# Sheet_1_copy.net
KiCad netlist of a schematic drawn in Altium Designer
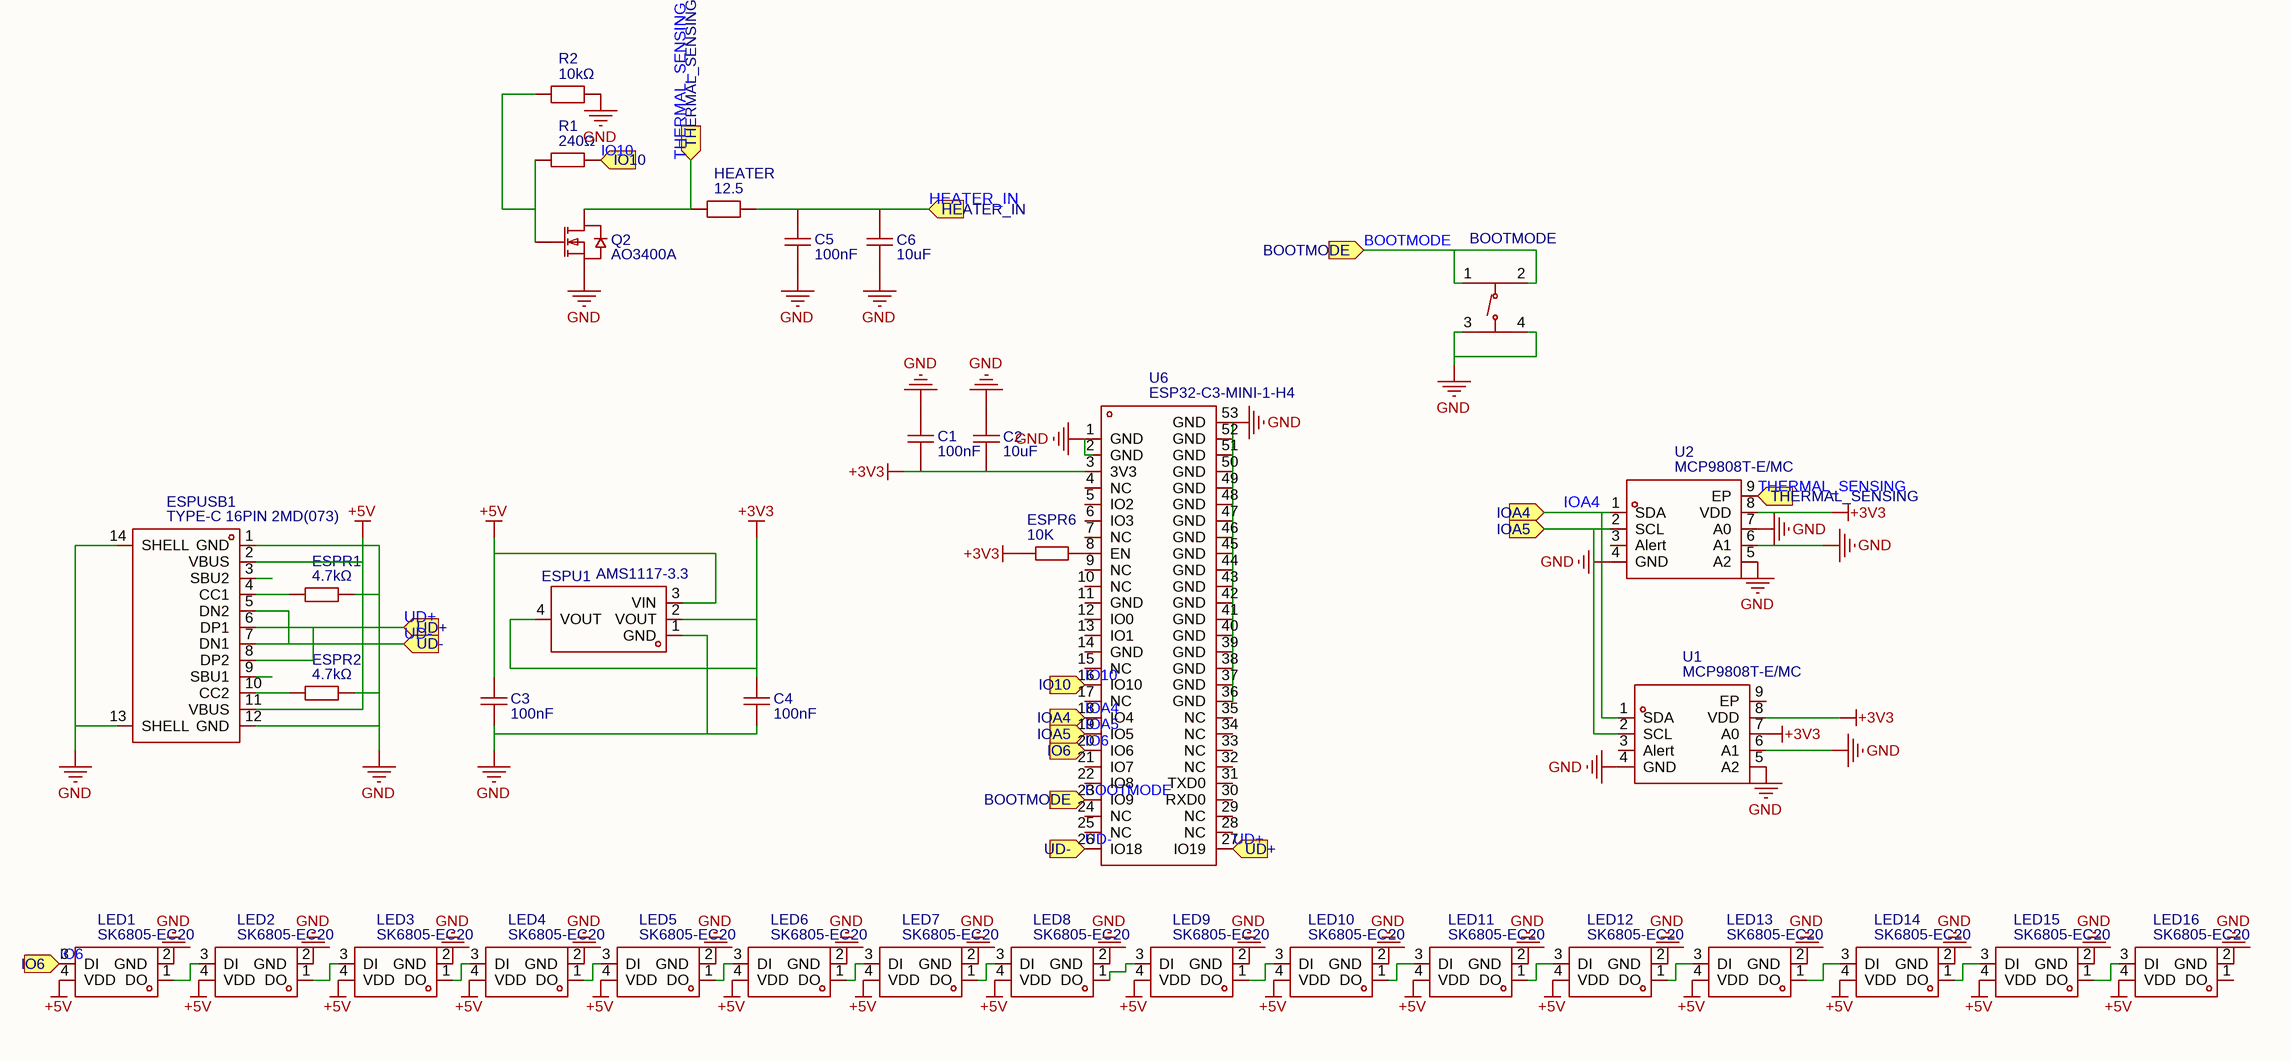
[diagram p0: Sheet_1 copy.schdoc]

(export (version "E")
  (design (tool "Eeschema 10.0.6"))
  (components
    (comp (ref "BOOTMODE")
      (value "TS-1187A-B-A-B")
      (footprint "SW-SMD_4P-L5.1-W5.1-P3.70-LS6.5-TL-2")
      (fields (field (name "MANUFACTURER") "XKB Connectivity(中国星坤)") (field (name "CONTRIBUTOR") "LCSC"))
      (libsource (lib "altium-import") (part "root_0_TS-1187A-B-A-B_"))
    )
    (comp (ref "C1")
      (value "100nF")
      (footprint "C0603")
      (fields
        (field (name "MANUFACTURER") "SAMSUNG(三星)")
        (field (name "MANUFACTURER PART") "CL10B104KB8NNNC")
      )
      (libsource (lib "altium-import") (part "root_1_100nF_"))
    )
    (comp (ref "C2")
      (value "10uF")
      (footprint "C0805")
      (fields
        (field (name "MANUFACTURER PART") "CL21A106KAYNNNE")
        (field (name "MANUFACTURER") "SAMSUNG(三星)")
      )
      (libsource (lib "altium-import") (part "root_3_10uF_"))
    )
    (comp (ref "C3")
      (value "100nF")
      (footprint "C0603")
      (fields
        (field (name "MANUFACTURER") "SAMSUNG(三星)")
        (field (name "MANUFACTURER PART") "CL10B104KB8NNNC")
      )
      (libsource (lib "altium-import") (part "root_1_100nF_"))
    )
    (comp (ref "C4")
      (value "100nF")
      (footprint "C0603")
      (fields
        (field (name "MANUFACTURER") "SAMSUNG(三星)")
        (field (name "MANUFACTURER PART") "CL10B104KB8NNNC")
      )
      (libsource (lib "altium-import") (part "root_1_100nF_"))
    )
    (comp (ref "C5")
      (value "100nF")
      (footprint "C0603")
      (fields
        (field (name "MANUFACTURER") "SAMSUNG(三星)")
        (field (name "MANUFACTURER PART") "CL10B104KB8NNNC")
      )
      (libsource (lib "altium-import") (part "root_1_100nF_"))
    )
    (comp (ref "C6")
      (value "10uF")
      (footprint "C0805")
      (fields
        (field (name "MANUFACTURER PART") "CL21A106KAYNNNE")
        (field (name "MANUFACTURER") "SAMSUNG(三星)")
      )
      (libsource (lib "altium-import") (part "root_3_10uF_"))
    )
    (comp (ref "ESPR1")
      (value "4.7kΩ")
      (footprint "R0402")
      (fields (field (name "MANUFACTURER") "UniOhm") (field (name "MANUFACTURER PART") "0402WGF4701TCE"))
      (libsource (lib "altium-import") (part "root_0_4.7kΩ_"))
    )
    (comp (ref "ESPR2")
      (value "4.7kΩ")
      (footprint "R0402")
      (fields (field (name "MANUFACTURER") "UniOhm") (field (name "MANUFACTURER PART") "0402WGF4701TCE"))
      (libsource (lib "altium-import") (part "root_0_4.7kΩ_"))
    )
    (comp (ref "ESPR6")
      (value "10K")
      (footprint "R0402")
      (fields (field (name "MANUFACTURER") "UniOhm") (field (name "MANUFACTURER PART") "0402WGF1002TCE"))
      (libsource (lib "altium-import") (part "root_2_10K_"))
    )
    (comp (ref "ESPU1")
      (value "AMS1117-3.3")
      (footprint "SOT-223-3_L6.5-W3.4-P2.30-LS7.0-BR")
      (fields (field (name "MANUFACTURER") "AMS"))
      (libsource (lib "altium-import") (part "root_0_AMS1117-3.3_"))
    )
    (comp (ref "ESPUSB1")
      (value "TYPE-C 16PIN 2MD(073)")
      (footprint "USB-C-SMD_TYPE-C-6PIN-2MD-073")
      (fields (field (name "MANUFACTURER") "SHOU HAN(首韩)") (field (name "CONTRIBUTOR") "LCSC"))
      (libsource (lib "altium-import") (part "root_2_TYPE-C 16PIN 2MD(073)_"))
    )
    (comp (ref "HEATER")
      (value "12.5")
      (fields (field (name "CONTRIBUTOR") "LCEDA_Lib"))
      (libsource (lib "altium-import") (part "root_0_12.5_"))
    )
    (comp (ref "LED1")
      (value "SK6805-EC20")
      (footprint "LED-SMD_4P-L2.0-W2.0-TL_WS2812B-2020")
      (fields (field (name "MANUFACTURER") "OPSCO Optoelectronics") (field (name "CONTRIBUTOR") "LCSC"))
      (libsource (lib "altium-import") (part "root_2_SK6805-EC20_"))
    )
    (comp (ref "LED2")
      (value "SK6805-EC20")
      (footprint "LED-SMD_4P-L2.0-W2.0-TL_WS2812B-2020")
      (fields (field (name "MANUFACTURER") "OPSCO Optoelectronics") (field (name "CONTRIBUTOR") "LCSC"))
      (libsource (lib "altium-import") (part "root_2_SK6805-EC20_"))
    )
    (comp (ref "LED3")
      (value "SK6805-EC20")
      (footprint "LED-SMD_4P-L2.0-W2.0-TL_WS2812B-2020")
      (fields (field (name "MANUFACTURER") "OPSCO Optoelectronics") (field (name "CONTRIBUTOR") "LCSC"))
      (libsource (lib "altium-import") (part "root_2_SK6805-EC20_"))
    )
    (comp (ref "LED4")
      (value "SK6805-EC20")
      (footprint "LED-SMD_4P-L2.0-W2.0-TL_WS2812B-2020")
      (fields (field (name "MANUFACTURER") "OPSCO Optoelectronics") (field (name "CONTRIBUTOR") "LCSC"))
      (libsource (lib "altium-import") (part "root_2_SK6805-EC20_"))
    )
    (comp (ref "LED5")
      (value "SK6805-EC20")
      (footprint "LED-SMD_4P-L2.0-W2.0-TL_WS2812B-2020")
      (fields (field (name "MANUFACTURER") "OPSCO Optoelectronics") (field (name "CONTRIBUTOR") "LCSC"))
      (libsource (lib "altium-import") (part "root_2_SK6805-EC20_"))
    )
    (comp (ref "LED6")
      (value "SK6805-EC20")
      (footprint "LED-SMD_4P-L2.0-W2.0-TL_WS2812B-2020")
      (fields (field (name "MANUFACTURER") "OPSCO Optoelectronics") (field (name "CONTRIBUTOR") "LCSC"))
      (libsource (lib "altium-import") (part "root_2_SK6805-EC20_"))
    )
    (comp (ref "LED7")
      (value "SK6805-EC20")
      (footprint "LED-SMD_4P-L2.0-W2.0-TL_WS2812B-2020")
      (fields (field (name "MANUFACTURER") "OPSCO Optoelectronics") (field (name "CONTRIBUTOR") "LCSC"))
      (libsource (lib "altium-import") (part "root_2_SK6805-EC20_"))
    )
    (comp (ref "LED8")
      (value "SK6805-EC20")
      (footprint "LED-SMD_4P-L2.0-W2.0-TL_WS2812B-2020")
      (fields (field (name "MANUFACTURER") "OPSCO Optoelectronics") (field (name "CONTRIBUTOR") "LCSC"))
      (libsource (lib "altium-import") (part "root_2_SK6805-EC20_"))
    )
    (comp (ref "LED9")
      (value "SK6805-EC20")
      (footprint "LED-SMD_4P-L2.0-W2.0-TL_WS2812B-2020")
      (fields (field (name "MANUFACTURER") "OPSCO Optoelectronics") (field (name "CONTRIBUTOR") "LCSC"))
      (libsource (lib "altium-import") (part "root_2_SK6805-EC20_"))
    )
    (comp (ref "LED10")
      (value "SK6805-EC20")
      (footprint "LED-SMD_4P-L2.0-W2.0-TL_WS2812B-2020")
      (fields (field (name "MANUFACTURER") "OPSCO Optoelectronics") (field (name "CONTRIBUTOR") "LCSC"))
      (libsource (lib "altium-import") (part "root_2_SK6805-EC20_"))
    )
    (comp (ref "LED11")
      (value "SK6805-EC20")
      (footprint "LED-SMD_4P-L2.0-W2.0-TL_WS2812B-2020")
      (fields (field (name "MANUFACTURER") "OPSCO Optoelectronics") (field (name "CONTRIBUTOR") "LCSC"))
      (libsource (lib "altium-import") (part "root_2_SK6805-EC20_"))
    )
    (comp (ref "LED12")
      (value "SK6805-EC20")
      (footprint "LED-SMD_4P-L2.0-W2.0-TL_WS2812B-2020")
      (fields (field (name "MANUFACTURER") "OPSCO Optoelectronics") (field (name "CONTRIBUTOR") "LCSC"))
      (libsource (lib "altium-import") (part "root_2_SK6805-EC20_"))
    )
    (comp (ref "LED13")
      (value "SK6805-EC20")
      (footprint "LED-SMD_4P-L2.0-W2.0-TL_WS2812B-2020")
      (fields (field (name "MANUFACTURER") "OPSCO Optoelectronics") (field (name "CONTRIBUTOR") "LCSC"))
      (libsource (lib "altium-import") (part "root_2_SK6805-EC20_"))
    )
    (comp (ref "LED14")
      (value "SK6805-EC20")
      (footprint "LED-SMD_4P-L2.0-W2.0-TL_WS2812B-2020")
      (fields (field (name "MANUFACTURER") "OPSCO Optoelectronics") (field (name "CONTRIBUTOR") "LCSC"))
      (libsource (lib "altium-import") (part "root_2_SK6805-EC20_"))
    )
    (comp (ref "LED15")
      (value "SK6805-EC20")
      (footprint "LED-SMD_4P-L2.0-W2.0-TL_WS2812B-2020")
      (fields (field (name "MANUFACTURER") "OPSCO Optoelectronics") (field (name "CONTRIBUTOR") "LCSC"))
      (libsource (lib "altium-import") (part "root_2_SK6805-EC20_"))
    )
    (comp (ref "LED16")
      (value "SK6805-EC20")
      (footprint "LED-SMD_4P-L2.0-W2.0-TL_WS2812B-2020")
      (fields (field (name "MANUFACTURER") "OPSCO Optoelectronics") (field (name "CONTRIBUTOR") "LCSC"))
      (libsource (lib "altium-import") (part "root_2_SK6805-EC20_"))
    )
    (comp (ref "Q2")
      (value "AO3400A")
      (footprint "SOT-23-3_L2.9-W1.3-P1.90-LS2.4-BR")
      (fields (field (name "MANUFACTURER") "AOS"))
      (libsource (lib "altium-import") (part "root_0_AO3400A_"))
    )
    (comp (ref "R1")
      (value "240Ω")
      (footprint "R0805")
      (fields (field (name "MANUFACTURER") "LIZ(丽智电子)") (field (name "MANUFACTURER PART") "CR0805J80241G"))
      (libsource (lib "altium-import") (part "root_0_240Ω_"))
    )
    (comp (ref "R2")
      (value "10kΩ")
      (footprint "R0805")
      (fields
        (field (name "MANUFACTURER") "Walsin(华新科)")
        (field (name "MANUFACTURER PART") "MR08X1002FTL")
        (field (name "CONTRIBUTOR") "LCSC")
      )
      (libsource (lib "altium-import") (part "root_0_10kΩ_"))
    )
    (comp (ref "U1")
      (value "MCP9808T-E/MC")
      (footprint "DFN-8_L3.0-W2.0-P0.50-TL-EP-1")
      (fields (field (name "MANUFACTURER") "MICROCHIP(美国微芯)") (field (name "CONTRIBUTOR") "lcsc"))
      (libsource (lib "altium-import") (part "root_0_MCP9808T-E/MC_"))
    )
    (comp (ref "U2")
      (value "MCP9808T-E/MC")
      (footprint "DFN-8_L3.0-W2.0-P0.50-TL-EP-1")
      (fields (field (name "MANUFACTURER") "MICROCHIP(美国微芯)") (field (name "CONTRIBUTOR") "lcsc"))
      (libsource (lib "altium-import") (part "root_0_MCP9808T-E/MC_"))
    )
    (comp (ref "U6")
      (value "ESP32-C3-MINI-1-H4")
      (footprint "WIFIM-SMD_ESP32-C3-MINI-1")
      (fields (field (name "MANUFACTURER") "ESPRESSIF(乐鑫)") (field (name "CONTRIBUTOR") "LCSC"))
      (libsource (lib "altium-import") (part "root_0_ESP32-C3-MINI-1-H4_"))
    )
  )
  (nets
    (net (code "1") (name "+3V3") (class "Default")
      (node (ref "C1") (pin "1") (pinfunction "1_1") (pintype "passive"))
      (node (ref "C2") (pin "2") (pinfunction "2_2") (pintype "passive"))
      (node (ref "C4") (pin "2") (pinfunction "2_2") (pintype "passive"))
      (node (ref "ESPR6") (pin "2") (pinfunction "2_2") (pintype "passive"))
      (node (ref "ESPU1") (pin "2") (pinfunction "VOUT_2") (pintype "passive"))
      (node (ref "ESPU1") (pin "4") (pinfunction "VOUT_4") (pintype "passive"))
      (node (ref "U1") (pin "7") (pinfunction "A0_7") (pintype "passive"))
      (node (ref "U1") (pin "8") (pinfunction "VDD_8") (pintype "passive"))
      (node (ref "U2") (pin "8") (pinfunction "VDD_8") (pintype "passive"))
      (node (ref "U6") (pin "3") (pinfunction "3V3_3") (pintype "passive"))
    )
    (net (code "2") (name "+5V") (class "Default")
      (node (ref "C3") (pin "2") (pinfunction "2_2") (pintype "passive"))
      (node (ref "ESPU1") (pin "3") (pinfunction "VIN_3") (pintype "passive"))
      (node (ref "ESPUSB1") (pin "11") (pinfunction "VBUS_11") (pintype "passive"))
      (node (ref "ESPUSB1") (pin "2") (pinfunction "VBUS_2") (pintype "passive"))
      (node (ref "LED1") (pin "4") (pinfunction "VDD_4") (pintype "passive"))
      (node (ref "LED10") (pin "4") (pinfunction "VDD_4") (pintype "passive"))
      (node (ref "LED11") (pin "4") (pinfunction "VDD_4") (pintype "passive"))
      (node (ref "LED12") (pin "4") (pinfunction "VDD_4") (pintype "passive"))
      (node (ref "LED13") (pin "4") (pinfunction "VDD_4") (pintype "passive"))
      (node (ref "LED14") (pin "4") (pinfunction "VDD_4") (pintype "passive"))
      (node (ref "LED15") (pin "4") (pinfunction "VDD_4") (pintype "passive"))
      (node (ref "LED16") (pin "4") (pinfunction "VDD_4") (pintype "passive"))
      (node (ref "LED2") (pin "4") (pinfunction "VDD_4") (pintype "passive"))
      (node (ref "LED3") (pin "4") (pinfunction "VDD_4") (pintype "passive"))
      (node (ref "LED4") (pin "4") (pinfunction "VDD_4") (pintype "passive"))
      (node (ref "LED5") (pin "4") (pinfunction "VDD_4") (pintype "passive"))
      (node (ref "LED6") (pin "4") (pinfunction "VDD_4") (pintype "passive"))
      (node (ref "LED7") (pin "4") (pinfunction "VDD_4") (pintype "passive"))
      (node (ref "LED8") (pin "4") (pinfunction "VDD_4") (pintype "passive"))
      (node (ref "LED9") (pin "4") (pinfunction "VDD_4") (pintype "passive"))
    )
    (net (code "3") (name "/BOOTMODE") (class "Default")
      (node (ref "BOOTMODE") (pin "1") (pinfunction "A_1") (pintype "passive"))
      (node (ref "BOOTMODE") (pin "2") (pinfunction "B_2") (pintype "passive"))
      (node (ref "U6") (pin "23") (pinfunction "IO9_23") (pintype "passive"))
    )
    (net (code "4") (name "/HEATER_IN") (class "Default")
      (node (ref "C5") (pin "2") (pinfunction "2_2") (pintype "passive"))
      (node (ref "C6") (pin "1") (pinfunction "1_1") (pintype "passive"))
      (node (ref "HEATER") (pin "2") (pinfunction "2_2") (pintype "passive"))
    )
    (net (code "5") (name "/IO6") (class "Default")
      (node (ref "LED1") (pin "3") (pinfunction "DI_3") (pintype "passive"))
      (node (ref "U6") (pin "20") (pinfunction "IO6_20") (pintype "passive"))
    )
    (net (code "6") (name "/IO10") (class "Default")
      (node (ref "R1") (pin "2") (pinfunction "2_2") (pintype "passive"))
      (node (ref "U6") (pin "16") (pinfunction "IO10_16") (pintype "passive"))
    )
    (net (code "7") (name "/IOA4") (class "Default")
      (node (ref "U1") (pin "1") (pinfunction "SDA_1") (pintype "passive"))
      (node (ref "U2") (pin "1") (pinfunction "SDA_1") (pintype "passive"))
      (node (ref "U6") (pin "18") (pinfunction "IO4_18") (pintype "passive"))
    )
    (net (code "8") (name "/IOA5") (class "Default")
      (node (ref "U1") (pin "2") (pinfunction "SCL_2") (pintype "passive"))
      (node (ref "U2") (pin "2") (pinfunction "SCL_2") (pintype "passive"))
      (node (ref "U6") (pin "19") (pinfunction "IO5_19") (pintype "passive"))
    )
    (net (code "9") (name "/THERMAL_SENSING") (class "Default")
      (node (ref "HEATER") (pin "1") (pinfunction "1_1") (pintype "passive"))
      (node (ref "Q2") (pin "3") (pinfunction "D_3") (pintype "passive"))
      (node (ref "U2") (pin "9") (pinfunction "EP_9") (pintype "passive"))
    )
    (net (code "10") (name "/UD+") (class "Default")
      (node (ref "ESPUSB1") (pin "6") (pinfunction "DP1_6") (pintype "passive"))
      (node (ref "ESPUSB1") (pin "8") (pinfunction "DP2_8") (pintype "passive"))
      (node (ref "U6") (pin "27") (pinfunction "IO19_27") (pintype "passive"))
    )
    (net (code "11") (name "/UD-") (class "Default")
      (node (ref "ESPUSB1") (pin "5") (pinfunction "DN2_5") (pintype "passive"))
      (node (ref "ESPUSB1") (pin "7") (pinfunction "DN1_7") (pintype "passive"))
      (node (ref "U6") (pin "26") (pinfunction "IO18_26") (pintype "passive"))
    )
    (net (code "12") (name "GND") (class "Default")
      (node (ref "BOOTMODE") (pin "3") (pinfunction "C_3") (pintype "passive"))
      (node (ref "BOOTMODE") (pin "4") (pinfunction "D_4") (pintype "passive"))
      (node (ref "C1") (pin "2") (pinfunction "2_2") (pintype "passive"))
      (node (ref "C2") (pin "1") (pinfunction "1_1") (pintype "passive"))
      (node (ref "C3") (pin "1") (pinfunction "1_1") (pintype "passive"))
      (node (ref "C4") (pin "1") (pinfunction "1_1") (pintype "passive"))
      (node (ref "C5") (pin "1") (pinfunction "1_1") (pintype "passive"))
      (node (ref "C6") (pin "2") (pinfunction "2_2") (pintype "passive"))
      (node (ref "ESPR1") (pin "2") (pinfunction "2_2") (pintype "passive"))
      (node (ref "ESPR2") (pin "2") (pinfunction "2_2") (pintype "passive"))
      (node (ref "ESPU1") (pin "1") (pinfunction "GND_1") (pintype "passive"))
      (node (ref "ESPUSB1") (pin "1") (pinfunction "GND_1") (pintype "passive"))
      (node (ref "ESPUSB1") (pin "12") (pinfunction "GND_12") (pintype "passive"))
      (node (ref "ESPUSB1") (pin "13") (pinfunction "SHELL_13") (pintype "passive"))
      (node (ref "ESPUSB1") (pin "14") (pinfunction "SHELL_14") (pintype "passive"))
      (node (ref "LED1") (pin "2") (pinfunction "GND_2") (pintype "passive"))
      (node (ref "LED10") (pin "2") (pinfunction "GND_2") (pintype "passive"))
      (node (ref "LED11") (pin "2") (pinfunction "GND_2") (pintype "passive"))
      (node (ref "LED12") (pin "2") (pinfunction "GND_2") (pintype "passive"))
      (node (ref "LED13") (pin "2") (pinfunction "GND_2") (pintype "passive"))
      (node (ref "LED14") (pin "2") (pinfunction "GND_2") (pintype "passive"))
      (node (ref "LED15") (pin "2") (pinfunction "GND_2") (pintype "passive"))
      (node (ref "LED16") (pin "2") (pinfunction "GND_2") (pintype "passive"))
      (node (ref "LED2") (pin "2") (pinfunction "GND_2") (pintype "passive"))
      (node (ref "LED3") (pin "2") (pinfunction "GND_2") (pintype "passive"))
      (node (ref "LED4") (pin "2") (pinfunction "GND_2") (pintype "passive"))
      (node (ref "LED5") (pin "2") (pinfunction "GND_2") (pintype "passive"))
      (node (ref "LED6") (pin "2") (pinfunction "GND_2") (pintype "passive"))
      (node (ref "LED7") (pin "2") (pinfunction "GND_2") (pintype "passive"))
      (node (ref "LED8") (pin "2") (pinfunction "GND_2") (pintype "passive"))
      (node (ref "LED9") (pin "2") (pinfunction "GND_2") (pintype "passive"))
      (node (ref "Q2") (pin "2") (pinfunction "S_2") (pintype "passive"))
      (node (ref "R2") (pin "2") (pinfunction "2_2") (pintype "passive"))
      (node (ref "U1") (pin "4") (pinfunction "GND_4") (pintype "passive"))
      (node (ref "U1") (pin "5") (pinfunction "A2_5") (pintype "passive"))
      (node (ref "U1") (pin "6") (pinfunction "A1_6") (pintype "passive"))
      (node (ref "U2") (pin "4") (pinfunction "GND_4") (pintype "passive"))
      (node (ref "U2") (pin "5") (pinfunction "A2_5") (pintype "passive"))
      (node (ref "U2") (pin "6") (pinfunction "A1_6") (pintype "passive"))
      (node (ref "U2") (pin "7") (pinfunction "A0_7") (pintype "passive"))
      (node (ref "U6") (pin "1") (pinfunction "GND_1") (pintype "passive"))
      (node (ref "U6") (pin "2") (pinfunction "GND_2") (pintype "passive"))
      (node (ref "U6") (pin "36") (pinfunction "GND_36") (pintype "passive"))
      (node (ref "U6") (pin "37") (pinfunction "GND_37") (pintype "passive"))
      (node (ref "U6") (pin "38") (pinfunction "GND_38") (pintype "passive"))
      (node (ref "U6") (pin "39") (pinfunction "GND_39") (pintype "passive"))
      (node (ref "U6") (pin "40") (pinfunction "GND_40") (pintype "passive"))
      (node (ref "U6") (pin "41") (pinfunction "GND_41") (pintype "passive"))
      (node (ref "U6") (pin "42") (pinfunction "GND_42") (pintype "passive"))
      (node (ref "U6") (pin "43") (pinfunction "GND_43") (pintype "passive"))
      (node (ref "U6") (pin "44") (pinfunction "GND_44") (pintype "passive"))
      (node (ref "U6") (pin "45") (pinfunction "GND_45") (pintype "passive"))
      (node (ref "U6") (pin "46") (pinfunction "GND_46") (pintype "passive"))
      (node (ref "U6") (pin "47") (pinfunction "GND_47") (pintype "passive"))
      (node (ref "U6") (pin "48") (pinfunction "GND_48") (pintype "passive"))
      (node (ref "U6") (pin "49") (pinfunction "GND_49") (pintype "passive"))
      (node (ref "U6") (pin "50") (pinfunction "GND_50") (pintype "passive"))
      (node (ref "U6") (pin "51") (pinfunction "GND_51") (pintype "passive"))
      (node (ref "U6") (pin "52") (pinfunction "GND_52") (pintype "passive"))
      (node (ref "U6") (pin "53") (pinfunction "GND_53") (pintype "passive"))
    )
    (net (code "13") (name "Net-(ESPUSB1-CC1)") (class "Default")
      (node (ref "ESPR1") (pin "1") (pinfunction "1_1") (pintype "passive"))
      (node (ref "ESPUSB1") (pin "4") (pinfunction "CC1_4") (pintype "passive"))
    )
    (net (code "14") (name "Net-(ESPUSB1-CC2)") (class "Default")
      (node (ref "ESPR2") (pin "1") (pinfunction "1_1") (pintype "passive"))
      (node (ref "ESPUSB1") (pin "10") (pinfunction "CC2_10") (pintype "passive"))
    )
    (net (code "15") (name "Net-(LED1-DO)") (class "Default")
      (node (ref "LED1") (pin "1") (pinfunction "DO_1") (pintype "passive"))
      (node (ref "LED2") (pin "3") (pinfunction "DI_3") (pintype "passive"))
    )
    (net (code "16") (name "Net-(LED2-DO)") (class "Default")
      (node (ref "LED2") (pin "1") (pinfunction "DO_1") (pintype "passive"))
      (node (ref "LED3") (pin "3") (pinfunction "DI_3") (pintype "passive"))
    )
    (net (code "17") (name "Net-(LED3-DO)") (class "Default")
      (node (ref "LED3") (pin "1") (pinfunction "DO_1") (pintype "passive"))
      (node (ref "LED4") (pin "3") (pinfunction "DI_3") (pintype "passive"))
    )
    (net (code "18") (name "Net-(LED4-DO)") (class "Default")
      (node (ref "LED4") (pin "1") (pinfunction "DO_1") (pintype "passive"))
      (node (ref "LED5") (pin "3") (pinfunction "DI_3") (pintype "passive"))
    )
    (net (code "19") (name "Net-(LED5-DO)") (class "Default")
      (node (ref "LED5") (pin "1") (pinfunction "DO_1") (pintype "passive"))
      (node (ref "LED6") (pin "3") (pinfunction "DI_3") (pintype "passive"))
    )
    (net (code "20") (name "Net-(LED6-DO)") (class "Default")
      (node (ref "LED6") (pin "1") (pinfunction "DO_1") (pintype "passive"))
      (node (ref "LED7") (pin "3") (pinfunction "DI_3") (pintype "passive"))
    )
    (net (code "21") (name "Net-(LED7-DO)") (class "Default")
      (node (ref "LED7") (pin "1") (pinfunction "DO_1") (pintype "passive"))
      (node (ref "LED8") (pin "3") (pinfunction "DI_3") (pintype "passive"))
    )
    (net (code "22") (name "Net-(LED8-DO)") (class "Default")
      (node (ref "LED8") (pin "1") (pinfunction "DO_1") (pintype "passive"))
      (node (ref "LED9") (pin "3") (pinfunction "DI_3") (pintype "passive"))
    )
    (net (code "23") (name "Net-(LED10-DI)") (class "Default")
      (node (ref "LED10") (pin "3") (pinfunction "DI_3") (pintype "passive"))
      (node (ref "LED9") (pin "1") (pinfunction "DO_1") (pintype "passive"))
    )
    (net (code "24") (name "Net-(LED10-DO)") (class "Default")
      (node (ref "LED10") (pin "1") (pinfunction "DO_1") (pintype "passive"))
      (node (ref "LED11") (pin "3") (pinfunction "DI_3") (pintype "passive"))
    )
    (net (code "25") (name "Net-(LED11-DO)") (class "Default")
      (node (ref "LED11") (pin "1") (pinfunction "DO_1") (pintype "passive"))
      (node (ref "LED12") (pin "3") (pinfunction "DI_3") (pintype "passive"))
    )
    (net (code "26") (name "Net-(LED12-DO)") (class "Default")
      (node (ref "LED12") (pin "1") (pinfunction "DO_1") (pintype "passive"))
      (node (ref "LED13") (pin "3") (pinfunction "DI_3") (pintype "passive"))
    )
    (net (code "27") (name "Net-(LED13-DO)") (class "Default")
      (node (ref "LED13") (pin "1") (pinfunction "DO_1") (pintype "passive"))
      (node (ref "LED14") (pin "3") (pinfunction "DI_3") (pintype "passive"))
    )
    (net (code "28") (name "Net-(LED14-DO)") (class "Default")
      (node (ref "LED14") (pin "1") (pinfunction "DO_1") (pintype "passive"))
      (node (ref "LED15") (pin "3") (pinfunction "DI_3") (pintype "passive"))
    )
    (net (code "29") (name "Net-(LED15-DO)") (class "Default")
      (node (ref "LED15") (pin "1") (pinfunction "DO_1") (pintype "passive"))
      (node (ref "LED16") (pin "3") (pinfunction "DI_3") (pintype "passive"))
    )
    (net (code "30") (name "Net-(Q2-G)") (class "Default")
      (node (ref "Q2") (pin "1") (pinfunction "G_1") (pintype "passive"))
      (node (ref "R1") (pin "1") (pinfunction "1_1") (pintype "passive"))
      (node (ref "R2") (pin "1") (pinfunction "1_1") (pintype "passive"))
    )
    (net (code "31") (name "Net-(U6-EN)") (class "Default")
      (node (ref "ESPR6") (pin "1") (pinfunction "1_1") (pintype "passive"))
      (node (ref "U6") (pin "8") (pinfunction "EN_8") (pintype "passive"))
    )
    (net (code "32") (name "unconnected-(ESPUSB1-SBU1-Pad9)") (class "Default")
      (node (ref "ESPUSB1") (pin "9") (pinfunction "SBU1_9") (pintype "passive"))
    )
    (net (code "33") (name "unconnected-(ESPUSB1-SBU2-Pad3)") (class "Default")
      (node (ref "ESPUSB1") (pin "3") (pinfunction "SBU2_3") (pintype "passive"))
    )
    (net (code "34") (name "unconnected-(LED16-DO-Pad1)") (class "Default")
      (node (ref "LED16") (pin "1") (pinfunction "DO_1") (pintype "passive"))
    )
    (net (code "35") (name "unconnected-(U1-Alert-Pad3)") (class "Default")
      (node (ref "U1") (pin "3") (pinfunction "Alert_3") (pintype "passive"))
    )
    (net (code "36") (name "unconnected-(U1-EP-Pad9)") (class "Default")
      (node (ref "U1") (pin "9") (pinfunction "EP_9") (pintype "passive"))
    )
    (net (code "37") (name "unconnected-(U2-Alert-Pad3)") (class "Default")
      (node (ref "U2") (pin "3") (pinfunction "Alert_3") (pintype "passive"))
    )
    (net (code "38") (name "unconnected-(U6-GND-Pad11)") (class "Default")
      (node (ref "U6") (pin "11") (pinfunction "GND_11") (pintype "passive"))
    )
    (net (code "39") (name "unconnected-(U6-GND-Pad14)") (class "Default")
      (node (ref "U6") (pin "14") (pinfunction "GND_14") (pintype "passive"))
    )
    (net (code "40") (name "unconnected-(U6-IO0-Pad12)") (class "Default")
      (node (ref "U6") (pin "12") (pinfunction "IO0_12") (pintype "passive"))
    )
    (net (code "41") (name "unconnected-(U6-IO1-Pad13)") (class "Default")
      (node (ref "U6") (pin "13") (pinfunction "IO1_13") (pintype "passive"))
    )
    (net (code "42") (name "unconnected-(U6-IO2-Pad5)") (class "Default")
      (node (ref "U6") (pin "5") (pinfunction "IO2_5") (pintype "passive"))
    )
    (net (code "43") (name "unconnected-(U6-IO3-Pad6)") (class "Default")
      (node (ref "U6") (pin "6") (pinfunction "IO3_6") (pintype "passive"))
    )
    (net (code "44") (name "unconnected-(U6-IO7-Pad21)") (class "Default")
      (node (ref "U6") (pin "21") (pinfunction "IO7_21") (pintype "passive"))
    )
    (net (code "45") (name "unconnected-(U6-IO8-Pad22)") (class "Default")
      (node (ref "U6") (pin "22") (pinfunction "IO8_22") (pintype "passive"))
    )
    (net (code "46") (name "unconnected-(U6-NC-Pad4)") (class "Default")
      (node (ref "U6") (pin "4") (pinfunction "NC_4") (pintype "passive"))
    )
    (net (code "47") (name "unconnected-(U6-NC-Pad7)") (class "Default")
      (node (ref "U6") (pin "7") (pinfunction "NC_7") (pintype "passive"))
    )
    (net (code "48") (name "unconnected-(U6-NC-Pad9)") (class "Default")
      (node (ref "U6") (pin "9") (pinfunction "NC_9") (pintype "passive"))
    )
    (net (code "49") (name "unconnected-(U6-NC-Pad10)") (class "Default")
      (node (ref "U6") (pin "10") (pinfunction "NC_10") (pintype "passive"))
    )
    (net (code "50") (name "unconnected-(U6-NC-Pad15)") (class "Default")
      (node (ref "U6") (pin "15") (pinfunction "NC_15") (pintype "passive"))
    )
    (net (code "51") (name "unconnected-(U6-NC-Pad17)") (class "Default")
      (node (ref "U6") (pin "17") (pinfunction "NC_17") (pintype "passive"))
    )
    (net (code "52") (name "unconnected-(U6-NC-Pad24)") (class "Default")
      (node (ref "U6") (pin "24") (pinfunction "NC_24") (pintype "passive"))
    )
    (net (code "53") (name "unconnected-(U6-NC-Pad25)") (class "Default")
      (node (ref "U6") (pin "25") (pinfunction "NC_25") (pintype "passive"))
    )
    (net (code "54") (name "unconnected-(U6-NC-Pad28)") (class "Default")
      (node (ref "U6") (pin "28") (pinfunction "NC_28") (pintype "passive"))
    )
    (net (code "55") (name "unconnected-(U6-NC-Pad29)") (class "Default")
      (node (ref "U6") (pin "29") (pinfunction "NC_29") (pintype "passive"))
    )
    (net (code "56") (name "unconnected-(U6-NC-Pad32)") (class "Default")
      (node (ref "U6") (pin "32") (pinfunction "NC_32") (pintype "passive"))
    )
    (net (code "57") (name "unconnected-(U6-NC-Pad33)") (class "Default")
      (node (ref "U6") (pin "33") (pinfunction "NC_33") (pintype "passive"))
    )
    (net (code "58") (name "unconnected-(U6-NC-Pad34)") (class "Default")
      (node (ref "U6") (pin "34") (pinfunction "NC_34") (pintype "passive"))
    )
    (net (code "59") (name "unconnected-(U6-NC-Pad35)") (class "Default")
      (node (ref "U6") (pin "35") (pinfunction "NC_35") (pintype "passive"))
    )
    (net (code "60") (name "unconnected-(U6-RXD0-Pad30)") (class "Default")
      (node (ref "U6") (pin "30") (pinfunction "RXD0_30") (pintype "passive"))
    )
    (net (code "61") (name "unconnected-(U6-TXD0-Pad31)") (class "Default")
      (node (ref "U6") (pin "31") (pinfunction "TXD0_31") (pintype "passive"))
    )
  )
)
